# Lamp_Matrix_and_GI_Driver.net
KiCad netlist of a schematic drawn in Altium Designer
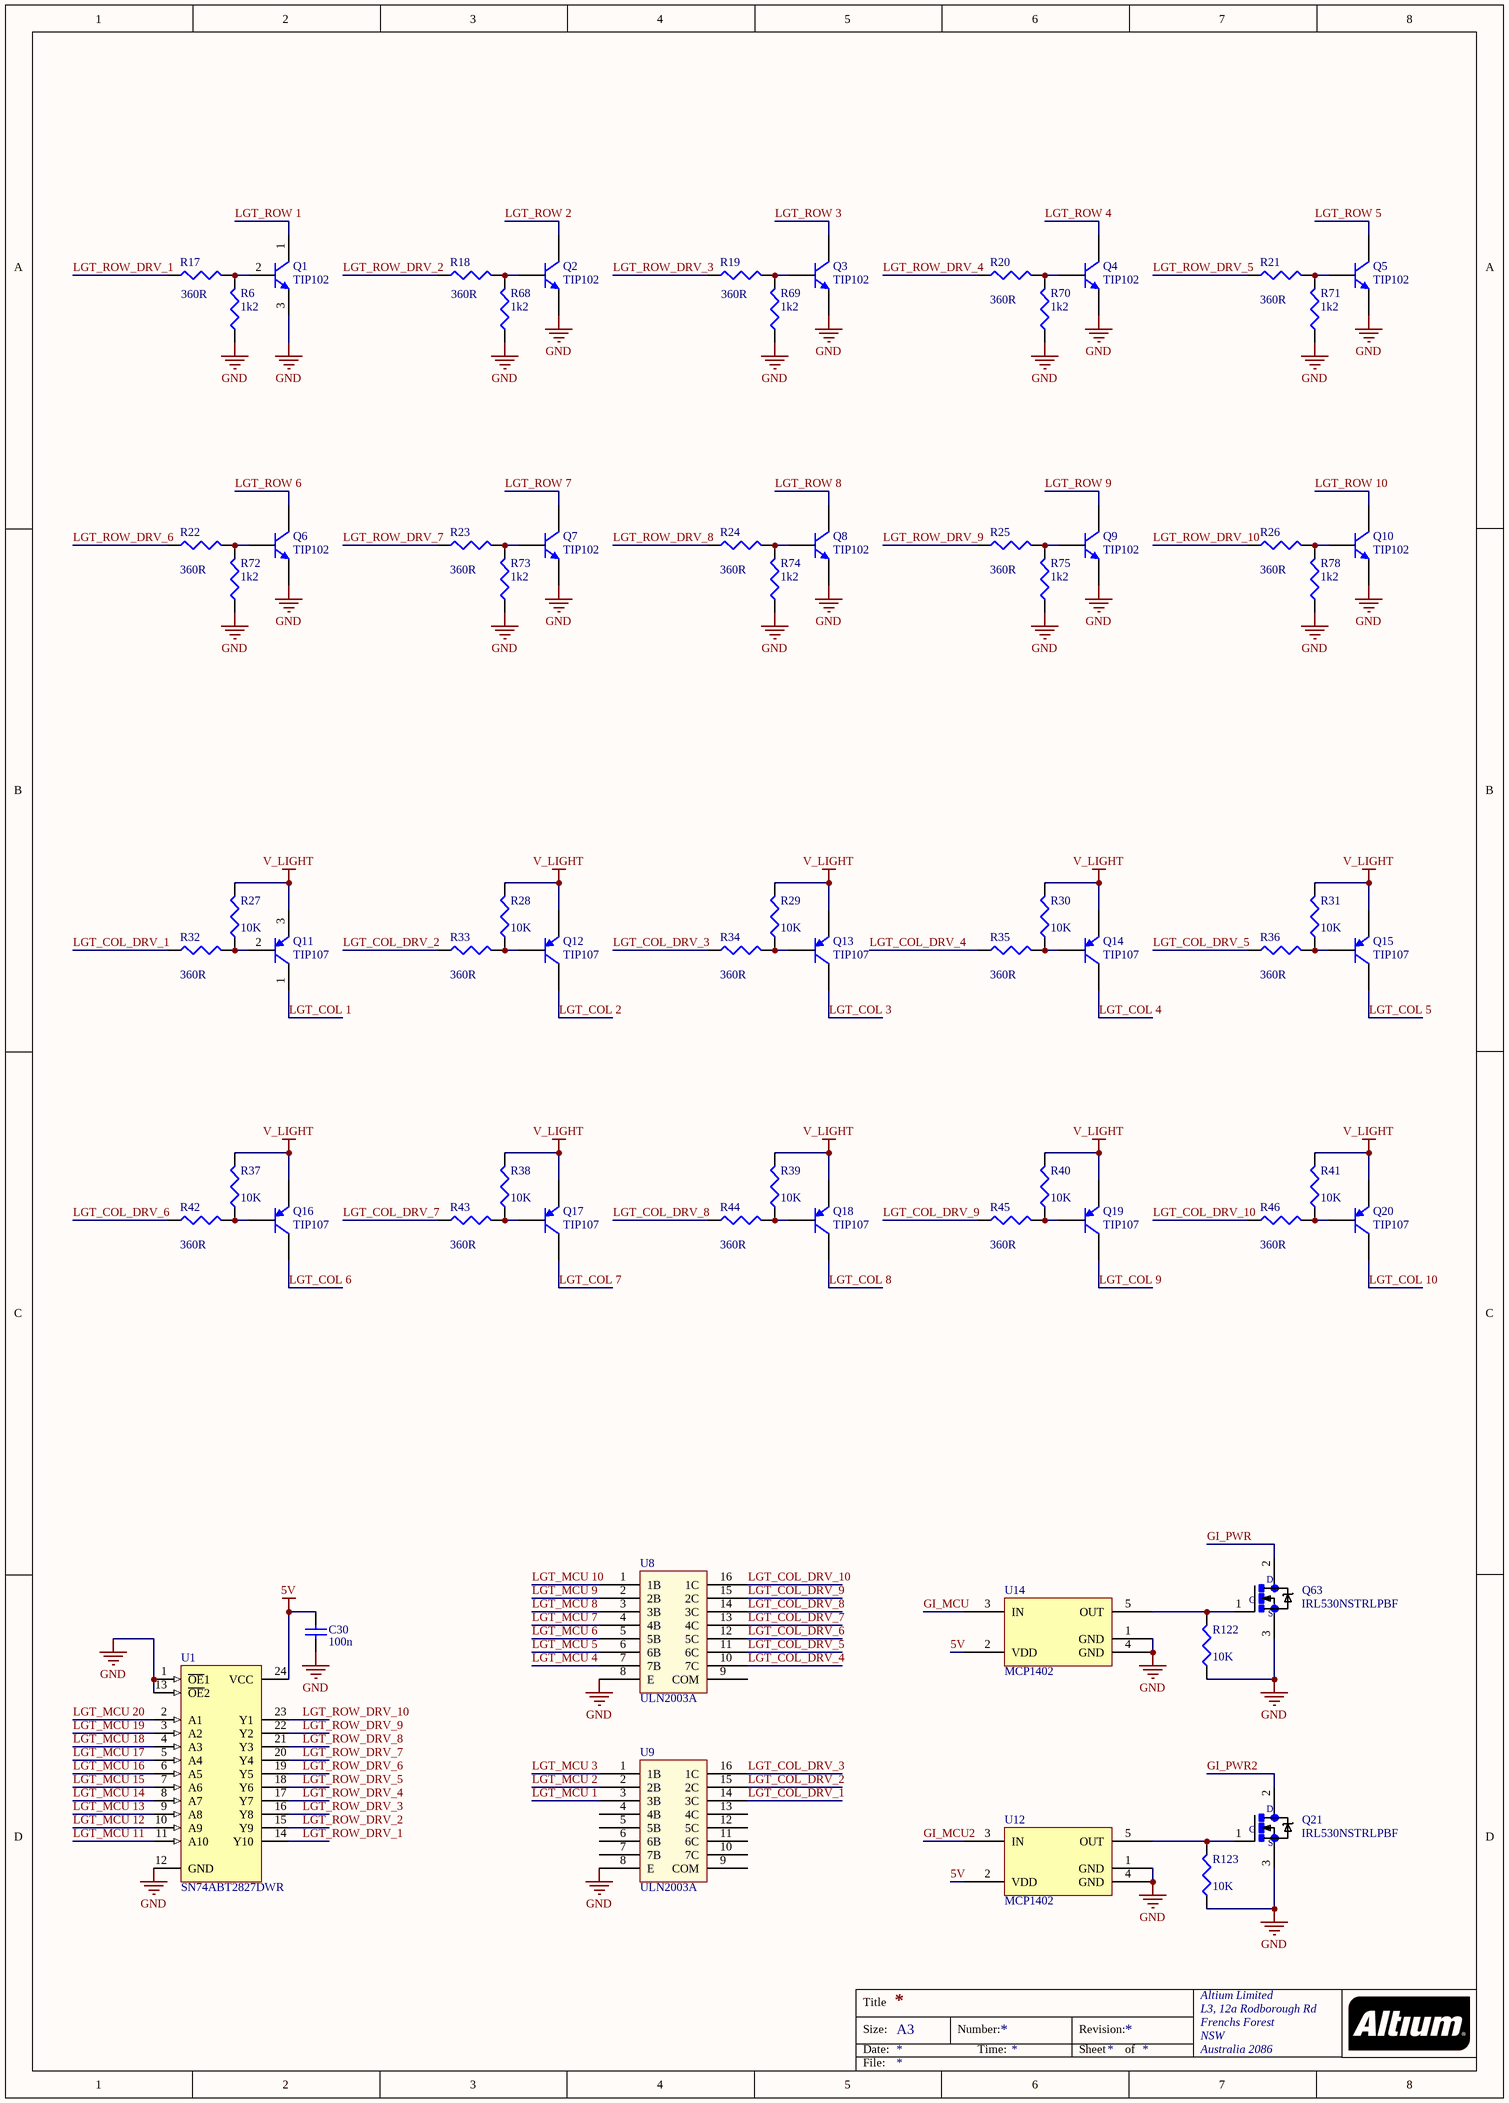
[diagram p0: Lamp Matrix and GI Driver.SchDoc]

(export (version "E")
  (design (tool "Eeschema 10.0.6"))
  (components
    (comp (ref "C30")
      (value "100n")
      (footprint "0805C-GENERIC")
      (description "Capacitor (Semiconductor SIM Model)")
      (fields (field (name "Comment") "Cap Semi") (field (name "PUBLISHER") "Altium Limited"))
      (libsource (lib "Miscellaneous Devices") (part "Cap Semi"))
    )
    (comp (ref "Q1")
      (value "TIP102")
      (footprint "TO-220AB")
      (description "NPN Bipolar Transistor")
      (fields (field (name "PUBLISHER") "Altium Limited"))
      (libsource (lib "Miscellaneous Devices") (part "NPN"))
    )
    (comp (ref "Q2")
      (value "TIP102")
      (footprint "TO-220AB")
      (description "NPN Bipolar Transistor")
      (fields (field (name "PUBLISHER") "Altium Limited"))
      (libsource (lib "") (part "NPN_1"))
    )
    (comp (ref "Q3")
      (value "TIP102")
      (footprint "TO-220AB")
      (description "NPN Bipolar Transistor")
      (fields (field (name "PUBLISHER") "Altium Limited"))
      (libsource (lib "") (part "NPN_1"))
    )
    (comp (ref "Q4")
      (value "TIP102")
      (footprint "TO-220AB")
      (description "NPN Bipolar Transistor")
      (fields (field (name "PUBLISHER") "Altium Limited"))
      (libsource (lib "") (part "NPN_1"))
    )
    (comp (ref "Q5")
      (value "TIP102")
      (footprint "TO-220AB")
      (description "NPN Bipolar Transistor")
      (fields (field (name "PUBLISHER") "Altium Limited"))
      (libsource (lib "") (part "NPN_1"))
    )
    (comp (ref "Q6")
      (value "TIP102")
      (footprint "TO-220AB")
      (description "NPN Bipolar Transistor")
      (fields (field (name "PUBLISHER") "Altium Limited"))
      (libsource (lib "") (part "NPN_1"))
    )
    (comp (ref "Q7")
      (value "TIP102")
      (footprint "TO-220AB")
      (description "NPN Bipolar Transistor")
      (fields (field (name "PUBLISHER") "Altium Limited"))
      (libsource (lib "") (part "NPN_1"))
    )
    (comp (ref "Q8")
      (value "TIP102")
      (footprint "TO-220AB")
      (description "NPN Bipolar Transistor")
      (fields (field (name "PUBLISHER") "Altium Limited"))
      (libsource (lib "") (part "NPN_1"))
    )
    (comp (ref "Q9")
      (value "TIP102")
      (footprint "TO-220AB")
      (description "NPN Bipolar Transistor")
      (fields (field (name "PUBLISHER") "Altium Limited"))
      (libsource (lib "") (part "NPN_1"))
    )
    (comp (ref "Q10")
      (value "TIP102")
      (footprint "TO-220AB")
      (description "NPN Bipolar Transistor")
      (fields (field (name "PUBLISHER") "Altium Limited"))
      (libsource (lib "") (part "NPN_1"))
    )
    (comp (ref "Q11")
      (value "TIP107")
      (footprint "TO-220AB")
      (description "PNP Bipolar Transistor")
      (fields (field (name "PUBLISHER") "Altium Limited"))
      (libsource (lib "Miscellaneous Devices") (part "PNP"))
    )
    (comp (ref "Q12")
      (value "TIP107")
      (footprint "TO-220AB")
      (description "PNP Bipolar Transistor")
      (fields (field (name "PUBLISHER") "Altium Limited"))
      (libsource (lib "") (part "PNP_1"))
    )
    (comp (ref "Q13")
      (value "TIP107")
      (footprint "TO-220AB")
      (description "PNP Bipolar Transistor")
      (fields (field (name "PUBLISHER") "Altium Limited"))
      (libsource (lib "") (part "PNP_1"))
    )
    (comp (ref "Q14")
      (value "TIP107")
      (footprint "TO-220AB")
      (description "PNP Bipolar Transistor")
      (fields (field (name "PUBLISHER") "Altium Limited"))
      (libsource (lib "") (part "PNP_1"))
    )
    (comp (ref "Q15")
      (value "TIP107")
      (footprint "TO-220AB")
      (description "PNP Bipolar Transistor")
      (fields (field (name "PUBLISHER") "Altium Limited"))
      (libsource (lib "") (part "PNP_1"))
    )
    (comp (ref "Q16")
      (value "TIP107")
      (footprint "TO-220AB")
      (description "PNP Bipolar Transistor")
      (fields (field (name "PUBLISHER") "Altium Limited"))
      (libsource (lib "") (part "PNP_1"))
    )
    (comp (ref "Q17")
      (value "TIP107")
      (footprint "TO-220AB")
      (description "PNP Bipolar Transistor")
      (fields (field (name "PUBLISHER") "Altium Limited"))
      (libsource (lib "") (part "PNP_1"))
    )
    (comp (ref "Q18")
      (value "TIP107")
      (footprint "TO-220AB")
      (description "PNP Bipolar Transistor")
      (fields (field (name "PUBLISHER") "Altium Limited"))
      (libsource (lib "") (part "PNP_1"))
    )
    (comp (ref "Q19")
      (value "TIP107")
      (footprint "TO-220AB")
      (description "PNP Bipolar Transistor")
      (fields (field (name "PUBLISHER") "Altium Limited"))
      (libsource (lib "") (part "PNP_1"))
    )
    (comp (ref "Q20")
      (value "TIP107")
      (footprint "TO-220AB")
      (description "PNP Bipolar Transistor")
      (fields (field (name "PUBLISHER") "Altium Limited"))
      (libsource (lib "") (part "PNP_1"))
    )
    (comp (ref "Q21")
      (value "IRL530NSTRLPBF")
      (footprint "TO-220AB")
      (description "MOSFET N-CH 100V 17A D2PAK")
      (fields (field (name "MF") "Infineon"))
      (libsource (lib "IRL530NSTRLPBF") (part "IRL530NSTRLPBF"))
    )
    (comp (ref "Q63")
      (value "IRL530NSTRLPBF")
      (footprint "TO-220AB")
      (description "MOSFET N-CH 100V 17A D2PAK")
      (fields (field (name "MF") "Infineon"))
      (libsource (lib "IRL530NSTRLPBF") (part "IRL530NSTRLPBF"))
    )
    (comp (ref "R6")
      (value "1k2")
      (footprint "0805R-GENERIC")
      (description "Resistor")
      (fields (field (name "Comment") "Res3") (field (name "PUBLISHER") "Altium Limited"))
      (libsource (lib "Miscellaneous Devices") (part "Res3"))
    )
    (comp (ref "R17")
      (value "360R")
      (footprint "0805R-GENERIC")
      (description "Resistor")
      (fields (field (name "Comment") "Res3") (field (name "PUBLISHER") "Altium Limited"))
      (libsource (lib "Miscellaneous Devices") (part "Res3"))
    )
    (comp (ref "R18")
      (value "360R")
      (footprint "0805R-GENERIC")
      (description "Resistor")
      (fields (field (name "Comment") "Res3") (field (name "PUBLISHER") "Altium Limited"))
      (libsource (lib "Miscellaneous Devices") (part "Res3"))
    )
    (comp (ref "R19")
      (value "360R")
      (footprint "0805R-GENERIC")
      (description "Resistor")
      (fields (field (name "Comment") "Res3") (field (name "PUBLISHER") "Altium Limited"))
      (libsource (lib "Miscellaneous Devices") (part "Res3"))
    )
    (comp (ref "R20")
      (value "360R")
      (footprint "0805R-GENERIC")
      (description "Resistor")
      (fields (field (name "Comment") "Res3") (field (name "PUBLISHER") "Altium Limited"))
      (libsource (lib "Miscellaneous Devices") (part "Res3"))
    )
    (comp (ref "R21")
      (value "360R")
      (footprint "0805R-GENERIC")
      (description "Resistor")
      (fields (field (name "Comment") "Res3") (field (name "PUBLISHER") "Altium Limited"))
      (libsource (lib "Miscellaneous Devices") (part "Res3"))
    )
    (comp (ref "R22")
      (value "360R")
      (footprint "0805R-GENERIC")
      (description "Resistor")
      (fields (field (name "Comment") "Res3") (field (name "PUBLISHER") "Altium Limited"))
      (libsource (lib "Miscellaneous Devices") (part "Res3"))
    )
    (comp (ref "R23")
      (value "360R")
      (footprint "0805R-GENERIC")
      (description "Resistor")
      (fields (field (name "Comment") "Res3") (field (name "PUBLISHER") "Altium Limited"))
      (libsource (lib "Miscellaneous Devices") (part "Res3"))
    )
    (comp (ref "R24")
      (value "360R")
      (footprint "0805R-GENERIC")
      (description "Resistor")
      (fields (field (name "Comment") "Res3") (field (name "PUBLISHER") "Altium Limited"))
      (libsource (lib "Miscellaneous Devices") (part "Res3"))
    )
    (comp (ref "R25")
      (value "360R")
      (footprint "0805R-GENERIC")
      (description "Resistor")
      (fields (field (name "Comment") "Res3") (field (name "PUBLISHER") "Altium Limited"))
      (libsource (lib "Miscellaneous Devices") (part "Res3"))
    )
    (comp (ref "R26")
      (value "360R")
      (footprint "0805R-GENERIC")
      (description "Resistor")
      (fields (field (name "Comment") "Res3") (field (name "PUBLISHER") "Altium Limited"))
      (libsource (lib "Miscellaneous Devices") (part "Res3"))
    )
    (comp (ref "R27")
      (value "10K")
      (footprint "0805R-GENERIC")
      (description "Resistor")
      (fields (field (name "Comment") "Res3") (field (name "PUBLISHER") "Altium Limited"))
      (libsource (lib "Miscellaneous Devices") (part "Res3"))
    )
    (comp (ref "R28")
      (value "10K")
      (footprint "0805R-GENERIC")
      (description "Resistor")
      (fields (field (name "Comment") "Res3") (field (name "PUBLISHER") "Altium Limited"))
      (libsource (lib "Miscellaneous Devices") (part "Res3"))
    )
    (comp (ref "R29")
      (value "10K")
      (footprint "0805R-GENERIC")
      (description "Resistor")
      (fields (field (name "Comment") "Res3") (field (name "PUBLISHER") "Altium Limited"))
      (libsource (lib "Miscellaneous Devices") (part "Res3"))
    )
    (comp (ref "R30")
      (value "10K")
      (footprint "0805R-GENERIC")
      (description "Resistor")
      (fields (field (name "Comment") "Res3") (field (name "PUBLISHER") "Altium Limited"))
      (libsource (lib "Miscellaneous Devices") (part "Res3"))
    )
    (comp (ref "R31")
      (value "10K")
      (footprint "0805R-GENERIC")
      (description "Resistor")
      (fields (field (name "Comment") "Res3") (field (name "PUBLISHER") "Altium Limited"))
      (libsource (lib "Miscellaneous Devices") (part "Res3"))
    )
    (comp (ref "R32")
      (value "360R")
      (footprint "0805R-GENERIC")
      (description "Resistor")
      (fields (field (name "Comment") "Res3") (field (name "PUBLISHER") "Altium Limited"))
      (libsource (lib "Miscellaneous Devices") (part "Res3"))
    )
    (comp (ref "R33")
      (value "360R")
      (footprint "0805R-GENERIC")
      (description "Resistor")
      (fields (field (name "Comment") "Res3") (field (name "PUBLISHER") "Altium Limited"))
      (libsource (lib "Miscellaneous Devices") (part "Res3"))
    )
    (comp (ref "R34")
      (value "360R")
      (footprint "0805R-GENERIC")
      (description "Resistor")
      (fields (field (name "Comment") "Res3") (field (name "PUBLISHER") "Altium Limited"))
      (libsource (lib "Miscellaneous Devices") (part "Res3"))
    )
    (comp (ref "R35")
      (value "360R")
      (footprint "0805R-GENERIC")
      (description "Resistor")
      (fields (field (name "Comment") "Res3") (field (name "PUBLISHER") "Altium Limited"))
      (libsource (lib "Miscellaneous Devices") (part "Res3"))
    )
    (comp (ref "R36")
      (value "360R")
      (footprint "0805R-GENERIC")
      (description "Resistor")
      (fields (field (name "Comment") "Res3") (field (name "PUBLISHER") "Altium Limited"))
      (libsource (lib "Miscellaneous Devices") (part "Res3"))
    )
    (comp (ref "R37")
      (value "10K")
      (footprint "0805R-GENERIC")
      (description "Resistor")
      (fields (field (name "Comment") "Res3") (field (name "PUBLISHER") "Altium Limited"))
      (libsource (lib "Miscellaneous Devices") (part "Res3"))
    )
    (comp (ref "R38")
      (value "10K")
      (footprint "0805R-GENERIC")
      (description "Resistor")
      (fields (field (name "Comment") "Res3") (field (name "PUBLISHER") "Altium Limited"))
      (libsource (lib "Miscellaneous Devices") (part "Res3"))
    )
    (comp (ref "R39")
      (value "10K")
      (footprint "0805R-GENERIC")
      (description "Resistor")
      (fields (field (name "Comment") "Res3") (field (name "PUBLISHER") "Altium Limited"))
      (libsource (lib "Miscellaneous Devices") (part "Res3"))
    )
    (comp (ref "R40")
      (value "10K")
      (footprint "0805R-GENERIC")
      (description "Resistor")
      (fields (field (name "Comment") "Res3") (field (name "PUBLISHER") "Altium Limited"))
      (libsource (lib "Miscellaneous Devices") (part "Res3"))
    )
    (comp (ref "R41")
      (value "10K")
      (footprint "0805R-GENERIC")
      (description "Resistor")
      (fields (field (name "Comment") "Res3") (field (name "PUBLISHER") "Altium Limited"))
      (libsource (lib "Miscellaneous Devices") (part "Res3"))
    )
    (comp (ref "R42")
      (value "360R")
      (footprint "0805R-GENERIC")
      (description "Resistor")
      (fields (field (name "Comment") "Res3") (field (name "PUBLISHER") "Altium Limited"))
      (libsource (lib "Miscellaneous Devices") (part "Res3"))
    )
    (comp (ref "R43")
      (value "360R")
      (footprint "0805R-GENERIC")
      (description "Resistor")
      (fields (field (name "Comment") "Res3") (field (name "PUBLISHER") "Altium Limited"))
      (libsource (lib "Miscellaneous Devices") (part "Res3"))
    )
    (comp (ref "R44")
      (value "360R")
      (footprint "0805R-GENERIC")
      (description "Resistor")
      (fields (field (name "Comment") "Res3") (field (name "PUBLISHER") "Altium Limited"))
      (libsource (lib "Miscellaneous Devices") (part "Res3"))
    )
    (comp (ref "R45")
      (value "360R")
      (footprint "0805R-GENERIC")
      (description "Resistor")
      (fields (field (name "Comment") "Res3") (field (name "PUBLISHER") "Altium Limited"))
      (libsource (lib "Miscellaneous Devices") (part "Res3"))
    )
    (comp (ref "R46")
      (value "360R")
      (footprint "0805R-GENERIC")
      (description "Resistor")
      (fields (field (name "Comment") "Res3") (field (name "PUBLISHER") "Altium Limited"))
      (libsource (lib "Miscellaneous Devices") (part "Res3"))
    )
    (comp (ref "R68")
      (value "1k2")
      (footprint "0805R-GENERIC")
      (description "Resistor")
      (fields (field (name "Comment") "Res3") (field (name "PUBLISHER") "Altium Limited"))
      (libsource (lib "Miscellaneous Devices") (part "Res3"))
    )
    (comp (ref "R69")
      (value "1k2")
      (footprint "0805R-GENERIC")
      (description "Resistor")
      (fields (field (name "Comment") "Res3") (field (name "PUBLISHER") "Altium Limited"))
      (libsource (lib "Miscellaneous Devices") (part "Res3"))
    )
    (comp (ref "R70")
      (value "1k2")
      (footprint "0805R-GENERIC")
      (description "Resistor")
      (fields (field (name "Comment") "Res3") (field (name "PUBLISHER") "Altium Limited"))
      (libsource (lib "Miscellaneous Devices") (part "Res3"))
    )
    (comp (ref "R71")
      (value "1k2")
      (footprint "0805R-GENERIC")
      (description "Resistor")
      (fields (field (name "Comment") "Res3") (field (name "PUBLISHER") "Altium Limited"))
      (libsource (lib "Miscellaneous Devices") (part "Res3"))
    )
    (comp (ref "R72")
      (value "1k2")
      (footprint "0805R-GENERIC")
      (description "Resistor")
      (fields (field (name "Comment") "Res3") (field (name "PUBLISHER") "Altium Limited"))
      (libsource (lib "Miscellaneous Devices") (part "Res3"))
    )
    (comp (ref "R73")
      (value "1k2")
      (footprint "0805R-GENERIC")
      (description "Resistor")
      (fields (field (name "Comment") "Res3") (field (name "PUBLISHER") "Altium Limited"))
      (libsource (lib "Miscellaneous Devices") (part "Res3"))
    )
    (comp (ref "R74")
      (value "1k2")
      (footprint "0805R-GENERIC")
      (description "Resistor")
      (fields (field (name "Comment") "Res3") (field (name "PUBLISHER") "Altium Limited"))
      (libsource (lib "Miscellaneous Devices") (part "Res3"))
    )
    (comp (ref "R75")
      (value "1k2")
      (footprint "0805R-GENERIC")
      (description "Resistor")
      (fields (field (name "Comment") "Res3") (field (name "PUBLISHER") "Altium Limited"))
      (libsource (lib "Miscellaneous Devices") (part "Res3"))
    )
    (comp (ref "R78")
      (value "1k2")
      (footprint "0805R-GENERIC")
      (description "Resistor")
      (fields (field (name "Comment") "Res3") (field (name "PUBLISHER") "Altium Limited"))
      (libsource (lib "Miscellaneous Devices") (part "Res3"))
    )
    (comp (ref "R122")
      (value "10K")
      (footprint "0805R-GENERIC")
      (description "Resistor")
      (fields (field (name "Comment") "Res3") (field (name "PUBLISHER") "Altium Limited"))
      (libsource (lib "Miscellaneous Devices") (part "Res3"))
    )
    (comp (ref "R123")
      (value "10K")
      (footprint "0805R-GENERIC")
      (description "Resistor")
      (fields (field (name "Comment") "Res3") (field (name "PUBLISHER") "Altium Limited"))
      (libsource (lib "Miscellaneous Devices") (part "Res3"))
    )
    (comp (ref "U1")
      (value "SN74ABT2827DWR")
      (footprint "SOIC24")
      (description "10-Bit Buffer/Driver with 3-State Outputs")
      (fields (field (name "PUBLISHER") "Altium Limited"))
      (libsource (lib "Texas_Instruments") (part "SN74LVC827ADW"))
    )
    (comp (ref "U8")
      (value "ULN2003A")
      (footprint "SOIC16")
      (libsource (lib "Texas_Instruments") (part "ULN2003A"))
    )
    (comp (ref "U9")
      (value "ULN2003A")
      (footprint "SOIC16")
      (libsource (lib "Texas_Instruments") (part "ULN2003A"))
    )
    (comp (ref "U12") (value "MCP1402") (footprint "SOT23-5") (libsource (lib "Microchip") (part "MCP1402")))
    (comp (ref "U14") (value "MCP1402") (footprint "SOT23-5") (libsource (lib "Microchip") (part "MCP1402")))
  )
  (nets
    (net (code "1") (name "/GI_MCU") (class "Default")
      (node (ref "U14") (pin "3") (pinfunction "IN_3") (pintype "passive"))
    )
    (net (code "2") (name "/GI_MCU2") (class "Default")
      (node (ref "U12") (pin "3") (pinfunction "IN_3") (pintype "passive"))
    )
    (net (code "3") (name "/GI_PWR") (class "Default")
      (node (ref "Q63") (pin "2") (pinfunction "D_2") (pintype "passive"))
    )
    (net (code "4") (name "/GI_PWR2") (class "Default")
      (node (ref "Q21") (pin "2") (pinfunction "D_2") (pintype "passive"))
    )
    (net (code "5") (name "/LGT_COL 1") (class "Default")
      (node (ref "Q11") (pin "1") (pinfunction "C_1") (pintype "passive"))
    )
    (net (code "6") (name "/LGT_COL 2") (class "Default")
      (node (ref "Q12") (pin "1") (pinfunction "C_1") (pintype "passive"))
    )
    (net (code "7") (name "/LGT_COL 3") (class "Default")
      (node (ref "Q13") (pin "1") (pinfunction "C_1") (pintype "passive"))
    )
    (net (code "8") (name "/LGT_COL 4") (class "Default")
      (node (ref "Q14") (pin "1") (pinfunction "C_1") (pintype "passive"))
    )
    (net (code "9") (name "/LGT_COL 5") (class "Default")
      (node (ref "Q15") (pin "1") (pinfunction "C_1") (pintype "passive"))
    )
    (net (code "10") (name "/LGT_COL 6") (class "Default")
      (node (ref "Q16") (pin "1") (pinfunction "C_1") (pintype "passive"))
    )
    (net (code "11") (name "/LGT_COL 7") (class "Default")
      (node (ref "Q17") (pin "1") (pinfunction "C_1") (pintype "passive"))
    )
    (net (code "12") (name "/LGT_COL 8") (class "Default")
      (node (ref "Q18") (pin "1") (pinfunction "C_1") (pintype "passive"))
    )
    (net (code "13") (name "/LGT_COL 9") (class "Default")
      (node (ref "Q19") (pin "1") (pinfunction "C_1") (pintype "passive"))
    )
    (net (code "14") (name "/LGT_COL 10") (class "Default")
      (node (ref "Q20") (pin "1") (pinfunction "C_1") (pintype "passive"))
    )
    (net (code "15") (name "/LGT_COL_DRV_1") (class "Default")
      (node (ref "R32") (pin "1") (pinfunction "1_1") (pintype "passive"))
      (node (ref "U9") (pin "14") (pinfunction "3C_14") (pintype "passive"))
    )
    (net (code "16") (name "/LGT_COL_DRV_2") (class "Default")
      (node (ref "R33") (pin "1") (pinfunction "1_1") (pintype "passive"))
      (node (ref "U9") (pin "15") (pinfunction "2C_15") (pintype "passive"))
    )
    (net (code "17") (name "/LGT_COL_DRV_3") (class "Default")
      (node (ref "R34") (pin "1") (pinfunction "1_1") (pintype "passive"))
      (node (ref "U9") (pin "16") (pinfunction "1C_16") (pintype "passive"))
    )
    (net (code "18") (name "/LGT_COL_DRV_4") (class "Default")
      (node (ref "R35") (pin "1") (pinfunction "1_1") (pintype "passive"))
      (node (ref "U8") (pin "10") (pinfunction "7C_10") (pintype "passive"))
    )
    (net (code "19") (name "/LGT_COL_DRV_5") (class "Default")
      (node (ref "R36") (pin "1") (pinfunction "1_1") (pintype "passive"))
      (node (ref "U8") (pin "11") (pinfunction "6C_11") (pintype "passive"))
    )
    (net (code "20") (name "/LGT_COL_DRV_6") (class "Default")
      (node (ref "R42") (pin "1") (pinfunction "1_1") (pintype "passive"))
      (node (ref "U8") (pin "12") (pinfunction "5C_12") (pintype "passive"))
    )
    (net (code "21") (name "/LGT_COL_DRV_7") (class "Default")
      (node (ref "R43") (pin "1") (pinfunction "1_1") (pintype "passive"))
      (node (ref "U8") (pin "13") (pinfunction "4C_13") (pintype "passive"))
    )
    (net (code "22") (name "/LGT_COL_DRV_8") (class "Default")
      (node (ref "R44") (pin "1") (pinfunction "1_1") (pintype "passive"))
      (node (ref "U8") (pin "14") (pinfunction "3C_14") (pintype "passive"))
    )
    (net (code "23") (name "/LGT_COL_DRV_9") (class "Default")
      (node (ref "R45") (pin "1") (pinfunction "1_1") (pintype "passive"))
      (node (ref "U8") (pin "15") (pinfunction "2C_15") (pintype "passive"))
    )
    (net (code "24") (name "/LGT_COL_DRV_10") (class "Default")
      (node (ref "R46") (pin "1") (pinfunction "1_1") (pintype "passive"))
      (node (ref "U8") (pin "16") (pinfunction "1C_16") (pintype "passive"))
    )
    (net (code "25") (name "/LGT_MCU 1") (class "Default")
      (node (ref "U9") (pin "3") (pinfunction "3B_3") (pintype "passive"))
    )
    (net (code "26") (name "/LGT_MCU 2") (class "Default")
      (node (ref "U9") (pin "2") (pinfunction "2B_2") (pintype "passive"))
    )
    (net (code "27") (name "/LGT_MCU 3") (class "Default")
      (node (ref "U9") (pin "1") (pinfunction "1B_1") (pintype "passive"))
    )
    (net (code "28") (name "/LGT_MCU 4") (class "Default")
      (node (ref "U8") (pin "7") (pinfunction "7B_7") (pintype "passive"))
    )
    (net (code "29") (name "/LGT_MCU 5") (class "Default")
      (node (ref "U8") (pin "6") (pinfunction "6B_6") (pintype "passive"))
    )
    (net (code "30") (name "/LGT_MCU 6") (class "Default")
      (node (ref "U8") (pin "5") (pinfunction "5B_5") (pintype "passive"))
    )
    (net (code "31") (name "/LGT_MCU 7") (class "Default")
      (node (ref "U8") (pin "4") (pinfunction "4B_4") (pintype "passive"))
    )
    (net (code "32") (name "/LGT_MCU 8") (class "Default")
      (node (ref "U8") (pin "3") (pinfunction "3B_3") (pintype "passive"))
    )
    (net (code "33") (name "/LGT_MCU 9") (class "Default")
      (node (ref "U8") (pin "2") (pinfunction "2B_2") (pintype "passive"))
    )
    (net (code "34") (name "/LGT_MCU 10") (class "Default")
      (node (ref "U8") (pin "1") (pinfunction "1B_1") (pintype "passive"))
    )
    (net (code "35") (name "/LGT_MCU 11") (class "Default")
      (node (ref "U1") (pin "11") (pinfunction "A10_11") (pintype "input"))
    )
    (net (code "36") (name "/LGT_MCU 12") (class "Default")
      (node (ref "U1") (pin "10") (pinfunction "A9_10") (pintype "input"))
    )
    (net (code "37") (name "/LGT_MCU 13") (class "Default")
      (node (ref "U1") (pin "9") (pinfunction "A8_9") (pintype "input"))
    )
    (net (code "38") (name "/LGT_MCU 14") (class "Default")
      (node (ref "U1") (pin "8") (pinfunction "A7_8") (pintype "input"))
    )
    (net (code "39") (name "/LGT_MCU 15") (class "Default")
      (node (ref "U1") (pin "7") (pinfunction "A6_7") (pintype "input"))
    )
    (net (code "40") (name "/LGT_MCU 16") (class "Default")
      (node (ref "U1") (pin "6") (pinfunction "A5_6") (pintype "input"))
    )
    (net (code "41") (name "/LGT_MCU 17") (class "Default")
      (node (ref "U1") (pin "5") (pinfunction "A4_5") (pintype "input"))
    )
    (net (code "42") (name "/LGT_MCU 18") (class "Default")
      (node (ref "U1") (pin "4") (pinfunction "A3_4") (pintype "input"))
    )
    (net (code "43") (name "/LGT_MCU 19") (class "Default")
      (node (ref "U1") (pin "3") (pinfunction "A2_3") (pintype "input"))
    )
    (net (code "44") (name "/LGT_MCU 20") (class "Default")
      (node (ref "U1") (pin "2") (pinfunction "A1_2") (pintype "input"))
    )
    (net (code "45") (name "/LGT_ROW 1") (class "Default")
      (node (ref "Q1") (pin "1") (pinfunction "C_1") (pintype "passive"))
    )
    (net (code "46") (name "/LGT_ROW 2") (class "Default")
      (node (ref "Q2") (pin "1") (pinfunction "C_1") (pintype "passive"))
    )
    (net (code "47") (name "/LGT_ROW 3") (class "Default")
      (node (ref "Q3") (pin "1") (pinfunction "C_1") (pintype "passive"))
    )
    (net (code "48") (name "/LGT_ROW 4") (class "Default")
      (node (ref "Q4") (pin "1") (pinfunction "C_1") (pintype "passive"))
    )
    (net (code "49") (name "/LGT_ROW 5") (class "Default")
      (node (ref "Q5") (pin "1") (pinfunction "C_1") (pintype "passive"))
    )
    (net (code "50") (name "/LGT_ROW 6") (class "Default")
      (node (ref "Q6") (pin "1") (pinfunction "C_1") (pintype "passive"))
    )
    (net (code "51") (name "/LGT_ROW 7") (class "Default")
      (node (ref "Q7") (pin "1") (pinfunction "C_1") (pintype "passive"))
    )
    (net (code "52") (name "/LGT_ROW 8") (class "Default")
      (node (ref "Q8") (pin "1") (pinfunction "C_1") (pintype "passive"))
    )
    (net (code "53") (name "/LGT_ROW 9") (class "Default")
      (node (ref "Q9") (pin "1") (pinfunction "C_1") (pintype "passive"))
    )
    (net (code "54") (name "/LGT_ROW 10") (class "Default")
      (node (ref "Q10") (pin "1") (pinfunction "C_1") (pintype "passive"))
    )
    (net (code "55") (name "/LGT_ROW_DRV_1") (class "Default")
      (node (ref "R17") (pin "1") (pinfunction "1_1") (pintype "passive"))
      (node (ref "U1") (pin "14") (pinfunction "Y10_14") (pintype "tri_state"))
    )
    (net (code "56") (name "/LGT_ROW_DRV_2") (class "Default")
      (node (ref "R18") (pin "1") (pinfunction "1_1") (pintype "passive"))
      (node (ref "U1") (pin "15") (pinfunction "Y9_15") (pintype "tri_state"))
    )
    (net (code "57") (name "/LGT_ROW_DRV_3") (class "Default")
      (node (ref "R19") (pin "1") (pinfunction "1_1") (pintype "passive"))
      (node (ref "U1") (pin "16") (pinfunction "Y8_16") (pintype "tri_state"))
    )
    (net (code "58") (name "/LGT_ROW_DRV_4") (class "Default")
      (node (ref "R20") (pin "1") (pinfunction "1_1") (pintype "passive"))
      (node (ref "U1") (pin "17") (pinfunction "Y7_17") (pintype "tri_state"))
    )
    (net (code "59") (name "/LGT_ROW_DRV_5") (class "Default")
      (node (ref "R21") (pin "1") (pinfunction "1_1") (pintype "passive"))
      (node (ref "U1") (pin "18") (pinfunction "Y6_18") (pintype "tri_state"))
    )
    (net (code "60") (name "/LGT_ROW_DRV_6") (class "Default")
      (node (ref "R22") (pin "1") (pinfunction "1_1") (pintype "passive"))
      (node (ref "U1") (pin "19") (pinfunction "Y5_19") (pintype "tri_state"))
    )
    (net (code "61") (name "/LGT_ROW_DRV_7") (class "Default")
      (node (ref "R23") (pin "1") (pinfunction "1_1") (pintype "passive"))
      (node (ref "U1") (pin "20") (pinfunction "Y4_20") (pintype "tri_state"))
    )
    (net (code "62") (name "/LGT_ROW_DRV_8") (class "Default")
      (node (ref "R24") (pin "1") (pinfunction "1_1") (pintype "passive"))
      (node (ref "U1") (pin "21") (pinfunction "Y3_21") (pintype "tri_state"))
    )
    (net (code "63") (name "/LGT_ROW_DRV_9") (class "Default")
      (node (ref "R25") (pin "1") (pinfunction "1_1") (pintype "passive"))
      (node (ref "U1") (pin "22") (pinfunction "Y2_22") (pintype "tri_state"))
    )
    (net (code "64") (name "/LGT_ROW_DRV_10") (class "Default")
      (node (ref "R26") (pin "1") (pinfunction "1_1") (pintype "passive"))
      (node (ref "U1") (pin "23") (pinfunction "Y1_23") (pintype "tri_state"))
    )
    (net (code "65") (name "5V") (class "Default")
      (node (ref "C30") (pin "2") (pinfunction "2_2") (pintype "passive"))
      (node (ref "U1") (pin "24") (pinfunction "VCC_24") (pintype "power_in"))
      (node (ref "U12") (pin "2") (pinfunction "VDD_2") (pintype "passive"))
      (node (ref "U14") (pin "2") (pinfunction "VDD_2") (pintype "passive"))
    )
    (net (code "66") (name "GND") (class "Default")
      (node (ref "C30") (pin "1") (pinfunction "1_1") (pintype "passive"))
      (node (ref "Q1") (pin "3") (pinfunction "E_3") (pintype "passive"))
      (node (ref "Q10") (pin "3") (pinfunction "E_3") (pintype "passive"))
      (node (ref "Q2") (pin "3") (pinfunction "E_3") (pintype "passive"))
      (node (ref "Q21") (pin "3") (pinfunction "S_3") (pintype "passive"))
      (node (ref "Q3") (pin "3") (pinfunction "E_3") (pintype "passive"))
      (node (ref "Q4") (pin "3") (pinfunction "E_3") (pintype "passive"))
      (node (ref "Q5") (pin "3") (pinfunction "E_3") (pintype "passive"))
      (node (ref "Q6") (pin "3") (pinfunction "E_3") (pintype "passive"))
      (node (ref "Q63") (pin "3") (pinfunction "S_3") (pintype "passive"))
      (node (ref "Q7") (pin "3") (pinfunction "E_3") (pintype "passive"))
      (node (ref "Q8") (pin "3") (pinfunction "E_3") (pintype "passive"))
      (node (ref "Q9") (pin "3") (pinfunction "E_3") (pintype "passive"))
      (node (ref "R122") (pin "1") (pinfunction "1_1") (pintype "passive"))
      (node (ref "R123") (pin "1") (pinfunction "1_1") (pintype "passive"))
      (node (ref "R6") (pin "1") (pinfunction "1_1") (pintype "passive"))
      (node (ref "R68") (pin "1") (pinfunction "1_1") (pintype "passive"))
      (node (ref "R69") (pin "1") (pinfunction "1_1") (pintype "passive"))
      (node (ref "R70") (pin "1") (pinfunction "1_1") (pintype "passive"))
      (node (ref "R71") (pin "1") (pinfunction "1_1") (pintype "passive"))
      (node (ref "R72") (pin "1") (pinfunction "1_1") (pintype "passive"))
      (node (ref "R73") (pin "1") (pinfunction "1_1") (pintype "passive"))
      (node (ref "R74") (pin "1") (pinfunction "1_1") (pintype "passive"))
      (node (ref "R75") (pin "1") (pinfunction "1_1") (pintype "passive"))
      (node (ref "R78") (pin "1") (pinfunction "1_1") (pintype "passive"))
      (node (ref "U1") (pin "1") (pinfunction "~{OE}1_1") (pintype "input"))
      (node (ref "U1") (pin "12") (pinfunction "GND_12") (pintype "power_in"))
      (node (ref "U1") (pin "13") (pinfunction "~{OE}2_13") (pintype "input"))
      (node (ref "U12") (pin "1") (pinfunction "GND_1") (pintype "passive"))
      (node (ref "U12") (pin "4") (pinfunction "GND_4") (pintype "passive"))
      (node (ref "U14") (pin "1") (pinfunction "GND_1") (pintype "passive"))
      (node (ref "U14") (pin "4") (pinfunction "GND_4") (pintype "passive"))
      (node (ref "U8") (pin "8") (pinfunction "E_8") (pintype "passive"))
      (node (ref "U9") (pin "8") (pinfunction "E_8") (pintype "passive"))
    )
    (net (code "67") (name "Net-(Q1-B)") (class "Default")
      (node (ref "Q1") (pin "2") (pinfunction "B_2") (pintype "passive"))
      (node (ref "R17") (pin "2") (pinfunction "2_2") (pintype "passive"))
      (node (ref "R6") (pin "2") (pinfunction "2_2") (pintype "passive"))
    )
    (net (code "68") (name "Net-(Q2-B)") (class "Default")
      (node (ref "Q2") (pin "2") (pinfunction "B_2") (pintype "passive"))
      (node (ref "R18") (pin "2") (pinfunction "2_2") (pintype "passive"))
      (node (ref "R68") (pin "2") (pinfunction "2_2") (pintype "passive"))
    )
    (net (code "69") (name "Net-(Q3-B)") (class "Default")
      (node (ref "Q3") (pin "2") (pinfunction "B_2") (pintype "passive"))
      (node (ref "R19") (pin "2") (pinfunction "2_2") (pintype "passive"))
      (node (ref "R69") (pin "2") (pinfunction "2_2") (pintype "passive"))
    )
    (net (code "70") (name "Net-(Q4-B)") (class "Default")
      (node (ref "Q4") (pin "2") (pinfunction "B_2") (pintype "passive"))
      (node (ref "R20") (pin "2") (pinfunction "2_2") (pintype "passive"))
      (node (ref "R70") (pin "2") (pinfunction "2_2") (pintype "passive"))
    )
    (net (code "71") (name "Net-(Q5-B)") (class "Default")
      (node (ref "Q5") (pin "2") (pinfunction "B_2") (pintype "passive"))
      (node (ref "R21") (pin "2") (pinfunction "2_2") (pintype "passive"))
      (node (ref "R71") (pin "2") (pinfunction "2_2") (pintype "passive"))
    )
    (net (code "72") (name "Net-(Q6-B)") (class "Default")
      (node (ref "Q6") (pin "2") (pinfunction "B_2") (pintype "passive"))
      (node (ref "R22") (pin "2") (pinfunction "2_2") (pintype "passive"))
      (node (ref "R72") (pin "2") (pinfunction "2_2") (pintype "passive"))
    )
    (net (code "73") (name "Net-(Q7-B)") (class "Default")
      (node (ref "Q7") (pin "2") (pinfunction "B_2") (pintype "passive"))
      (node (ref "R23") (pin "2") (pinfunction "2_2") (pintype "passive"))
      (node (ref "R73") (pin "2") (pinfunction "2_2") (pintype "passive"))
    )
    (net (code "74") (name "Net-(Q8-B)") (class "Default")
      (node (ref "Q8") (pin "2") (pinfunction "B_2") (pintype "passive"))
      (node (ref "R24") (pin "2") (pinfunction "2_2") (pintype "passive"))
      (node (ref "R74") (pin "2") (pinfunction "2_2") (pintype "passive"))
    )
    (net (code "75") (name "Net-(Q9-B)") (class "Default")
      (node (ref "Q9") (pin "2") (pinfunction "B_2") (pintype "passive"))
      (node (ref "R25") (pin "2") (pinfunction "2_2") (pintype "passive"))
      (node (ref "R75") (pin "2") (pinfunction "2_2") (pintype "passive"))
    )
    (net (code "76") (name "Net-(Q10-B)") (class "Default")
      (node (ref "Q10") (pin "2") (pinfunction "B_2") (pintype "passive"))
      (node (ref "R26") (pin "2") (pinfunction "2_2") (pintype "passive"))
      (node (ref "R78") (pin "2") (pinfunction "2_2") (pintype "passive"))
    )
    (net (code "77") (name "Net-(Q11-B)") (class "Default")
      (node (ref "Q11") (pin "2") (pinfunction "B_2") (pintype "passive"))
      (node (ref "R27") (pin "1") (pinfunction "1_1") (pintype "passive"))
      (node (ref "R32") (pin "2") (pinfunction "2_2") (pintype "passive"))
    )
    (net (code "78") (name "Net-(Q12-B)") (class "Default")
      (node (ref "Q12") (pin "2") (pinfunction "B_2") (pintype "passive"))
      (node (ref "R28") (pin "1") (pinfunction "1_1") (pintype "passive"))
      (node (ref "R33") (pin "2") (pinfunction "2_2") (pintype "passive"))
    )
    (net (code "79") (name "Net-(Q13-B)") (class "Default")
      (node (ref "Q13") (pin "2") (pinfunction "B_2") (pintype "passive"))
      (node (ref "R29") (pin "1") (pinfunction "1_1") (pintype "passive"))
      (node (ref "R34") (pin "2") (pinfunction "2_2") (pintype "passive"))
    )
    (net (code "80") (name "Net-(Q14-B)") (class "Default")
      (node (ref "Q14") (pin "2") (pinfunction "B_2") (pintype "passive"))
      (node (ref "R30") (pin "1") (pinfunction "1_1") (pintype "passive"))
      (node (ref "R35") (pin "2") (pinfunction "2_2") (pintype "passive"))
    )
    (net (code "81") (name "Net-(Q15-B)") (class "Default")
      (node (ref "Q15") (pin "2") (pinfunction "B_2") (pintype "passive"))
      (node (ref "R31") (pin "1") (pinfunction "1_1") (pintype "passive"))
      (node (ref "R36") (pin "2") (pinfunction "2_2") (pintype "passive"))
    )
    (net (code "82") (name "Net-(Q16-B)") (class "Default")
      (node (ref "Q16") (pin "2") (pinfunction "B_2") (pintype "passive"))
      (node (ref "R37") (pin "1") (pinfunction "1_1") (pintype "passive"))
      (node (ref "R42") (pin "2") (pinfunction "2_2") (pintype "passive"))
    )
    (net (code "83") (name "Net-(Q17-B)") (class "Default")
      (node (ref "Q17") (pin "2") (pinfunction "B_2") (pintype "passive"))
      (node (ref "R38") (pin "1") (pinfunction "1_1") (pintype "passive"))
      (node (ref "R43") (pin "2") (pinfunction "2_2") (pintype "passive"))
    )
    (net (code "84") (name "Net-(Q18-B)") (class "Default")
      (node (ref "Q18") (pin "2") (pinfunction "B_2") (pintype "passive"))
      (node (ref "R39") (pin "1") (pinfunction "1_1") (pintype "passive"))
      (node (ref "R44") (pin "2") (pinfunction "2_2") (pintype "passive"))
    )
    (net (code "85") (name "Net-(Q19-B)") (class "Default")
      (node (ref "Q19") (pin "2") (pinfunction "B_2") (pintype "passive"))
      (node (ref "R40") (pin "1") (pinfunction "1_1") (pintype "passive"))
      (node (ref "R45") (pin "2") (pinfunction "2_2") (pintype "passive"))
    )
    (net (code "86") (name "Net-(Q20-B)") (class "Default")
      (node (ref "Q20") (pin "2") (pinfunction "B_2") (pintype "passive"))
      (node (ref "R41") (pin "1") (pinfunction "1_1") (pintype "passive"))
      (node (ref "R46") (pin "2") (pinfunction "2_2") (pintype "passive"))
    )
    (net (code "87") (name "Net-(Q21-G)") (class "Default")
      (node (ref "Q21") (pin "1") (pinfunction "G_1") (pintype "passive"))
      (node (ref "R123") (pin "2") (pinfunction "2_2") (pintype "passive"))
      (node (ref "U12") (pin "5") (pinfunction "OUT_5") (pintype "passive"))
    )
    (net (code "88") (name "Net-(Q63-G)") (class "Default")
      (node (ref "Q63") (pin "1") (pinfunction "G_1") (pintype "passive"))
      (node (ref "R122") (pin "2") (pinfunction "2_2") (pintype "passive"))
      (node (ref "U14") (pin "5") (pinfunction "OUT_5") (pintype "passive"))
    )
    (net (code "89") (name "V_LIGHT") (class "Default")
      (node (ref "Q11") (pin "3") (pinfunction "E_3") (pintype "passive"))
      (node (ref "Q12") (pin "3") (pinfunction "E_3") (pintype "passive"))
      (node (ref "Q13") (pin "3") (pinfunction "E_3") (pintype "passive"))
      (node (ref "Q14") (pin "3") (pinfunction "E_3") (pintype "passive"))
      (node (ref "Q15") (pin "3") (pinfunction "E_3") (pintype "passive"))
      (node (ref "Q16") (pin "3") (pinfunction "E_3") (pintype "passive"))
      (node (ref "Q17") (pin "3") (pinfunction "E_3") (pintype "passive"))
      (node (ref "Q18") (pin "3") (pinfunction "E_3") (pintype "passive"))
      (node (ref "Q19") (pin "3") (pinfunction "E_3") (pintype "passive"))
      (node (ref "Q20") (pin "3") (pinfunction "E_3") (pintype "passive"))
      (node (ref "R27") (pin "2") (pinfunction "2_2") (pintype "passive"))
      (node (ref "R28") (pin "2") (pinfunction "2_2") (pintype "passive"))
      (node (ref "R29") (pin "2") (pinfunction "2_2") (pintype "passive"))
      (node (ref "R30") (pin "2") (pinfunction "2_2") (pintype "passive"))
      (node (ref "R31") (pin "2") (pinfunction "2_2") (pintype "passive"))
      (node (ref "R37") (pin "2") (pinfunction "2_2") (pintype "passive"))
      (node (ref "R38") (pin "2") (pinfunction "2_2") (pintype "passive"))
      (node (ref "R39") (pin "2") (pinfunction "2_2") (pintype "passive"))
      (node (ref "R40") (pin "2") (pinfunction "2_2") (pintype "passive"))
      (node (ref "R41") (pin "2") (pinfunction "2_2") (pintype "passive"))
    )
    (net (code "90") (name "unconnected-(U8-COM-Pad9)") (class "Default")
      (node (ref "U8") (pin "9") (pinfunction "COM_9") (pintype "passive"))
    )
    (net (code "91") (name "unconnected-(U9-4B-Pad4)") (class "Default")
      (node (ref "U9") (pin "4") (pinfunction "4B_4") (pintype "passive"))
    )
    (net (code "92") (name "unconnected-(U9-4C-Pad13)") (class "Default")
      (node (ref "U9") (pin "13") (pinfunction "4C_13") (pintype "passive"))
    )
    (net (code "93") (name "unconnected-(U9-5B-Pad5)") (class "Default")
      (node (ref "U9") (pin "5") (pinfunction "5B_5") (pintype "passive"))
    )
    (net (code "94") (name "unconnected-(U9-5C-Pad12)") (class "Default")
      (node (ref "U9") (pin "12") (pinfunction "5C_12") (pintype "passive"))
    )
    (net (code "95") (name "unconnected-(U9-6B-Pad6)") (class "Default")
      (node (ref "U9") (pin "6") (pinfunction "6B_6") (pintype "passive"))
    )
    (net (code "96") (name "unconnected-(U9-6C-Pad11)") (class "Default")
      (node (ref "U9") (pin "11") (pinfunction "6C_11") (pintype "passive"))
    )
    (net (code "97") (name "unconnected-(U9-7B-Pad7)") (class "Default")
      (node (ref "U9") (pin "7") (pinfunction "7B_7") (pintype "passive"))
    )
    (net (code "98") (name "unconnected-(U9-7C-Pad10)") (class "Default")
      (node (ref "U9") (pin "10") (pinfunction "7C_10") (pintype "passive"))
    )
    (net (code "99") (name "unconnected-(U9-COM-Pad9)") (class "Default")
      (node (ref "U9") (pin "9") (pinfunction "COM_9") (pintype "passive"))
    )
  )
)
